# tiny13_charlie4_50mm.net
KiCad netlist of a schematic drawn in EAGLE
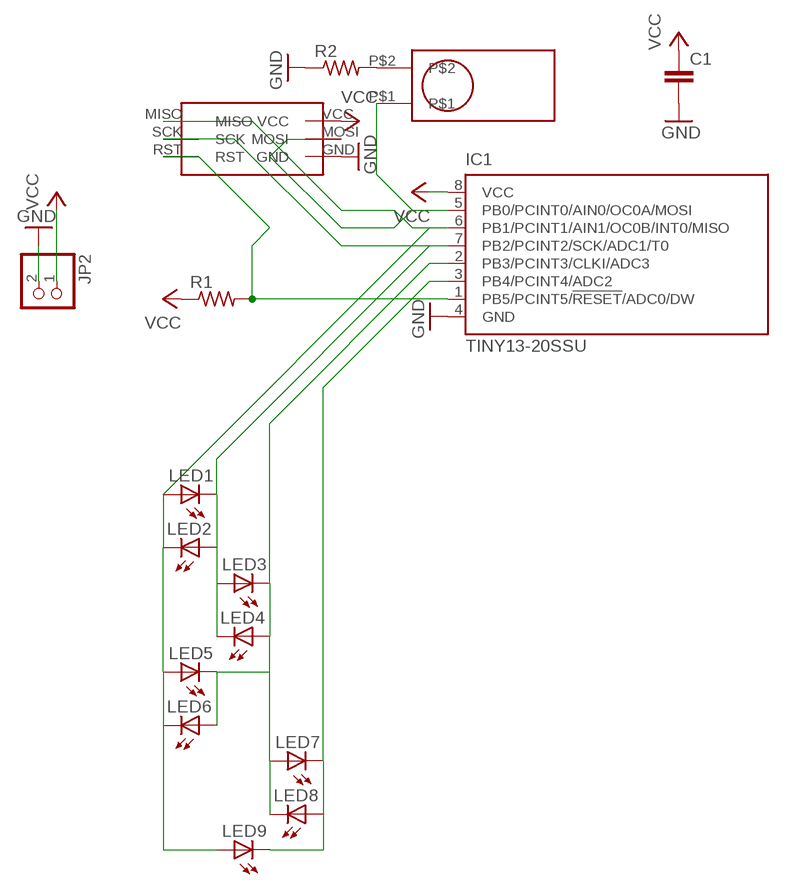
[diagram p0: schematic, sheet 1]

(export (version "E")
  (design (tool "Eeschema 10.0.6"))
  (components
    (comp (ref "C1")
      (value "C-EU025-025X050")
      (footprint "eagle-import:C025-025X050")
      (libsource (lib "eagle-import") (part "C-EU025-025X050"))
    )
    (comp (ref "IC1")
      (value "TINY13-20SSU")
      (footprint "eagle-import:8S1")
      (fields (field (name "MPN") "ATTINY13-20SSU"))
      (libsource (lib "eagle-import") (part "TINY13SSU-20"))
    )
    (comp (ref "JP2")
      (value "PINHD-1X2/90")
      (footprint "eagle-import:1X02_90")
      (libsource (lib "eagle-import") (part "PINHD-1X2/90"))
    )
    (comp (ref "LED1")
      (value "LED3MM")
      (footprint "eagle-import:LED3MM")
      (libsource (lib "eagle-import") (part "LED3MM"))
    )
    (comp (ref "LED2")
      (value "LED3MM")
      (footprint "eagle-import:LED3MM")
      (libsource (lib "eagle-import") (part "LED3MM"))
    )
    (comp (ref "LED3")
      (value "LED3MM")
      (footprint "eagle-import:LED3MM")
      (libsource (lib "eagle-import") (part "LED3MM"))
    )
    (comp (ref "LED4")
      (value "LED3MM")
      (footprint "eagle-import:LED3MM")
      (libsource (lib "eagle-import") (part "LED3MM"))
    )
    (comp (ref "LED5")
      (value "LED3MM")
      (footprint "eagle-import:LED3MM")
      (libsource (lib "eagle-import") (part "LED3MM"))
    )
    (comp (ref "LED6")
      (value "LED3MM")
      (footprint "eagle-import:LED3MM")
      (libsource (lib "eagle-import") (part "LED3MM"))
    )
    (comp (ref "LED7")
      (value "LED3MM")
      (footprint "eagle-import:LED3MM")
      (libsource (lib "eagle-import") (part "LED3MM"))
    )
    (comp (ref "LED8")
      (value "LED3MM")
      (footprint "eagle-import:LED3MM")
      (libsource (lib "eagle-import") (part "LED3MM"))
    )
    (comp (ref "LED9")
      (value "LED3MM")
      (footprint "eagle-import:LED3MM")
      (libsource (lib "eagle-import") (part "LED3MM"))
    )
    (comp (ref "R1")
      (value "R-US_0207/7")
      (footprint "eagle-import:0207_7")
      (libsource (lib "eagle-import") (part "R-US_0207/7"))
    )
    (comp (ref "R2")
      (value "R-US_0207/7")
      (footprint "eagle-import:0207_7")
      (libsource (lib "eagle-import") (part "R-US_0207/7"))
    )
    (comp (ref "U$1")
      (value "TILT_SWITCH_MECHANICAL")
      (footprint "eagle-import:TILT_SWITCH_MECHANICAL")
      (libsource (lib "eagle-import") (part "TILT_SWITCH_MECHANICAL"))
    )
    (comp (ref "U$2")
      (value "AVR_ISP_6_PIN_1X6_SMT_CONTACT_PROGRAMMER")
      (footprint "eagle-import:CONTACT_ISP_PROGRAMMER_1X6_ATMEL")
      (libsource (lib "eagle-import") (part "AVR_ISP_6_PIN_1X6_SMT_CONTACT_PROGRAMMER"))
    )
  )
  (nets
    (net (code "1") (name "GND") (class "Default")
      (node (ref "C1") (pin "2") (pinfunction "2_2") (pintype "passive"))
      (node (ref "IC1") (pin "4") (pinfunction "GND_4") (pintype "power_in"))
      (node (ref "JP2") (pin "2") (pinfunction "2_2") (pintype "passive"))
      (node (ref "R2") (pin "1") (pinfunction "1_1") (pintype "passive"))
      (node (ref "U$2") (pin "GND") (pinfunction "GND_GND") (pintype "bidirectional"))
    )
    (net (code "2") (name "Net-(IC1-PB0{slash}PCINT0{slash}AIN0{slash}OC0A{slash}MOSI)") (class "Default")
      (node (ref "IC1") (pin "5") (pinfunction "PB0/PCINT0/AIN0/OC0A/MOSI_5") (pintype "bidirectional"))
      (node (ref "U$1") (pin "P$1") (pinfunction "P$1_P$1") (pintype "bidirectional"))
      (node (ref "U$2") (pin "MOSI") (pinfunction "MOSI_MOSI") (pintype "bidirectional"))
    )
    (net (code "3") (name "Net-(IC1-PB1{slash}PCINT1{slash}AIN1{slash}OC0B{slash}INT0{slash}MISO)") (class "Default")
      (node (ref "IC1") (pin "6") (pinfunction "PB1/PCINT1/AIN1/OC0B/INT0/MISO_6") (pintype "bidirectional"))
      (node (ref "LED1") (pin "A") (pinfunction "A_A") (pintype "passive"))
      (node (ref "LED2") (pin "K") (pinfunction "C_K") (pintype "passive"))
      (node (ref "LED5") (pin "A") (pinfunction "A_A") (pintype "passive"))
      (node (ref "LED6") (pin "K") (pinfunction "C_K") (pintype "passive"))
      (node (ref "LED9") (pin "A") (pinfunction "A_A") (pintype "passive"))
      (node (ref "U$2") (pin "MISO") (pinfunction "MISO_MISO") (pintype "bidirectional"))
    )
    (net (code "4") (name "Net-(IC1-PB2{slash}PCINT2{slash}SCK{slash}ADC1{slash}T0)") (class "Default")
      (node (ref "IC1") (pin "7") (pinfunction "PB2/PCINT2/SCK/ADC1/T0_7") (pintype "bidirectional"))
      (node (ref "LED1") (pin "K") (pinfunction "C_K") (pintype "passive"))
      (node (ref "LED2") (pin "A") (pinfunction "A_A") (pintype "passive"))
      (node (ref "LED3") (pin "A") (pinfunction "A_A") (pintype "passive"))
      (node (ref "LED4") (pin "K") (pinfunction "C_K") (pintype "passive"))
      (node (ref "U$2") (pin "SCK") (pinfunction "SCK_SCK") (pintype "bidirectional"))
    )
    (net (code "5") (name "Net-(IC1-PB3{slash}PCINT3{slash}CLKI{slash}ADC3)") (class "Default")
      (node (ref "IC1") (pin "2") (pinfunction "PB3/PCINT3/CLKI/ADC3_2") (pintype "bidirectional"))
      (node (ref "LED3") (pin "K") (pinfunction "C_K") (pintype "passive"))
      (node (ref "LED4") (pin "A") (pinfunction "A_A") (pintype "passive"))
      (node (ref "LED5") (pin "K") (pinfunction "C_K") (pintype "passive"))
      (node (ref "LED6") (pin "A") (pinfunction "A_A") (pintype "passive"))
      (node (ref "LED7") (pin "A") (pinfunction "A_A") (pintype "passive"))
      (node (ref "LED8") (pin "K") (pinfunction "C_K") (pintype "passive"))
    )
    (net (code "6") (name "Net-(IC1-PB4{slash}PCINT4{slash}ADC2)") (class "Default")
      (node (ref "IC1") (pin "3") (pinfunction "PB4/PCINT4/ADC2_3") (pintype "bidirectional"))
      (node (ref "LED7") (pin "K") (pinfunction "C_K") (pintype "passive"))
      (node (ref "LED8") (pin "A") (pinfunction "A_A") (pintype "passive"))
      (node (ref "LED9") (pin "K") (pinfunction "C_K") (pintype "passive"))
    )
    (net (code "7") (name "Net-(IC1-PB5{slash}PCINT5{slash}~{RESET}{slash}ADC0{slash}DW)") (class "Default")
      (node (ref "IC1") (pin "1") (pinfunction "PB5/PCINT5/~{RESET}/ADC0/DW_1") (pintype "bidirectional"))
      (node (ref "R1") (pin "2") (pinfunction "2_2") (pintype "passive"))
      (node (ref "U$2") (pin "RST") (pinfunction "RST_RST") (pintype "bidirectional"))
    )
    (net (code "8") (name "Net-(R2-Pad2)") (class "Default")
      (node (ref "R2") (pin "2") (pinfunction "2_2") (pintype "passive"))
      (node (ref "U$1") (pin "P$2") (pinfunction "P$2_P$2") (pintype "bidirectional"))
    )
    (net (code "9") (name "VCC") (class "Default")
      (node (ref "C1") (pin "1") (pinfunction "1_1") (pintype "passive"))
      (node (ref "IC1") (pin "8") (pinfunction "VCC_8") (pintype "power_in"))
      (node (ref "JP2") (pin "1") (pinfunction "1_1") (pintype "passive"))
      (node (ref "R1") (pin "1") (pinfunction "1_1") (pintype "passive"))
      (node (ref "U$2") (pin "VCC") (pinfunction "VCC_VCC") (pintype "bidirectional"))
    )
  )
)
